# 04-8A34004_DPLL-2.net
KiCad netlist of a schematic drawn in Altium Designer
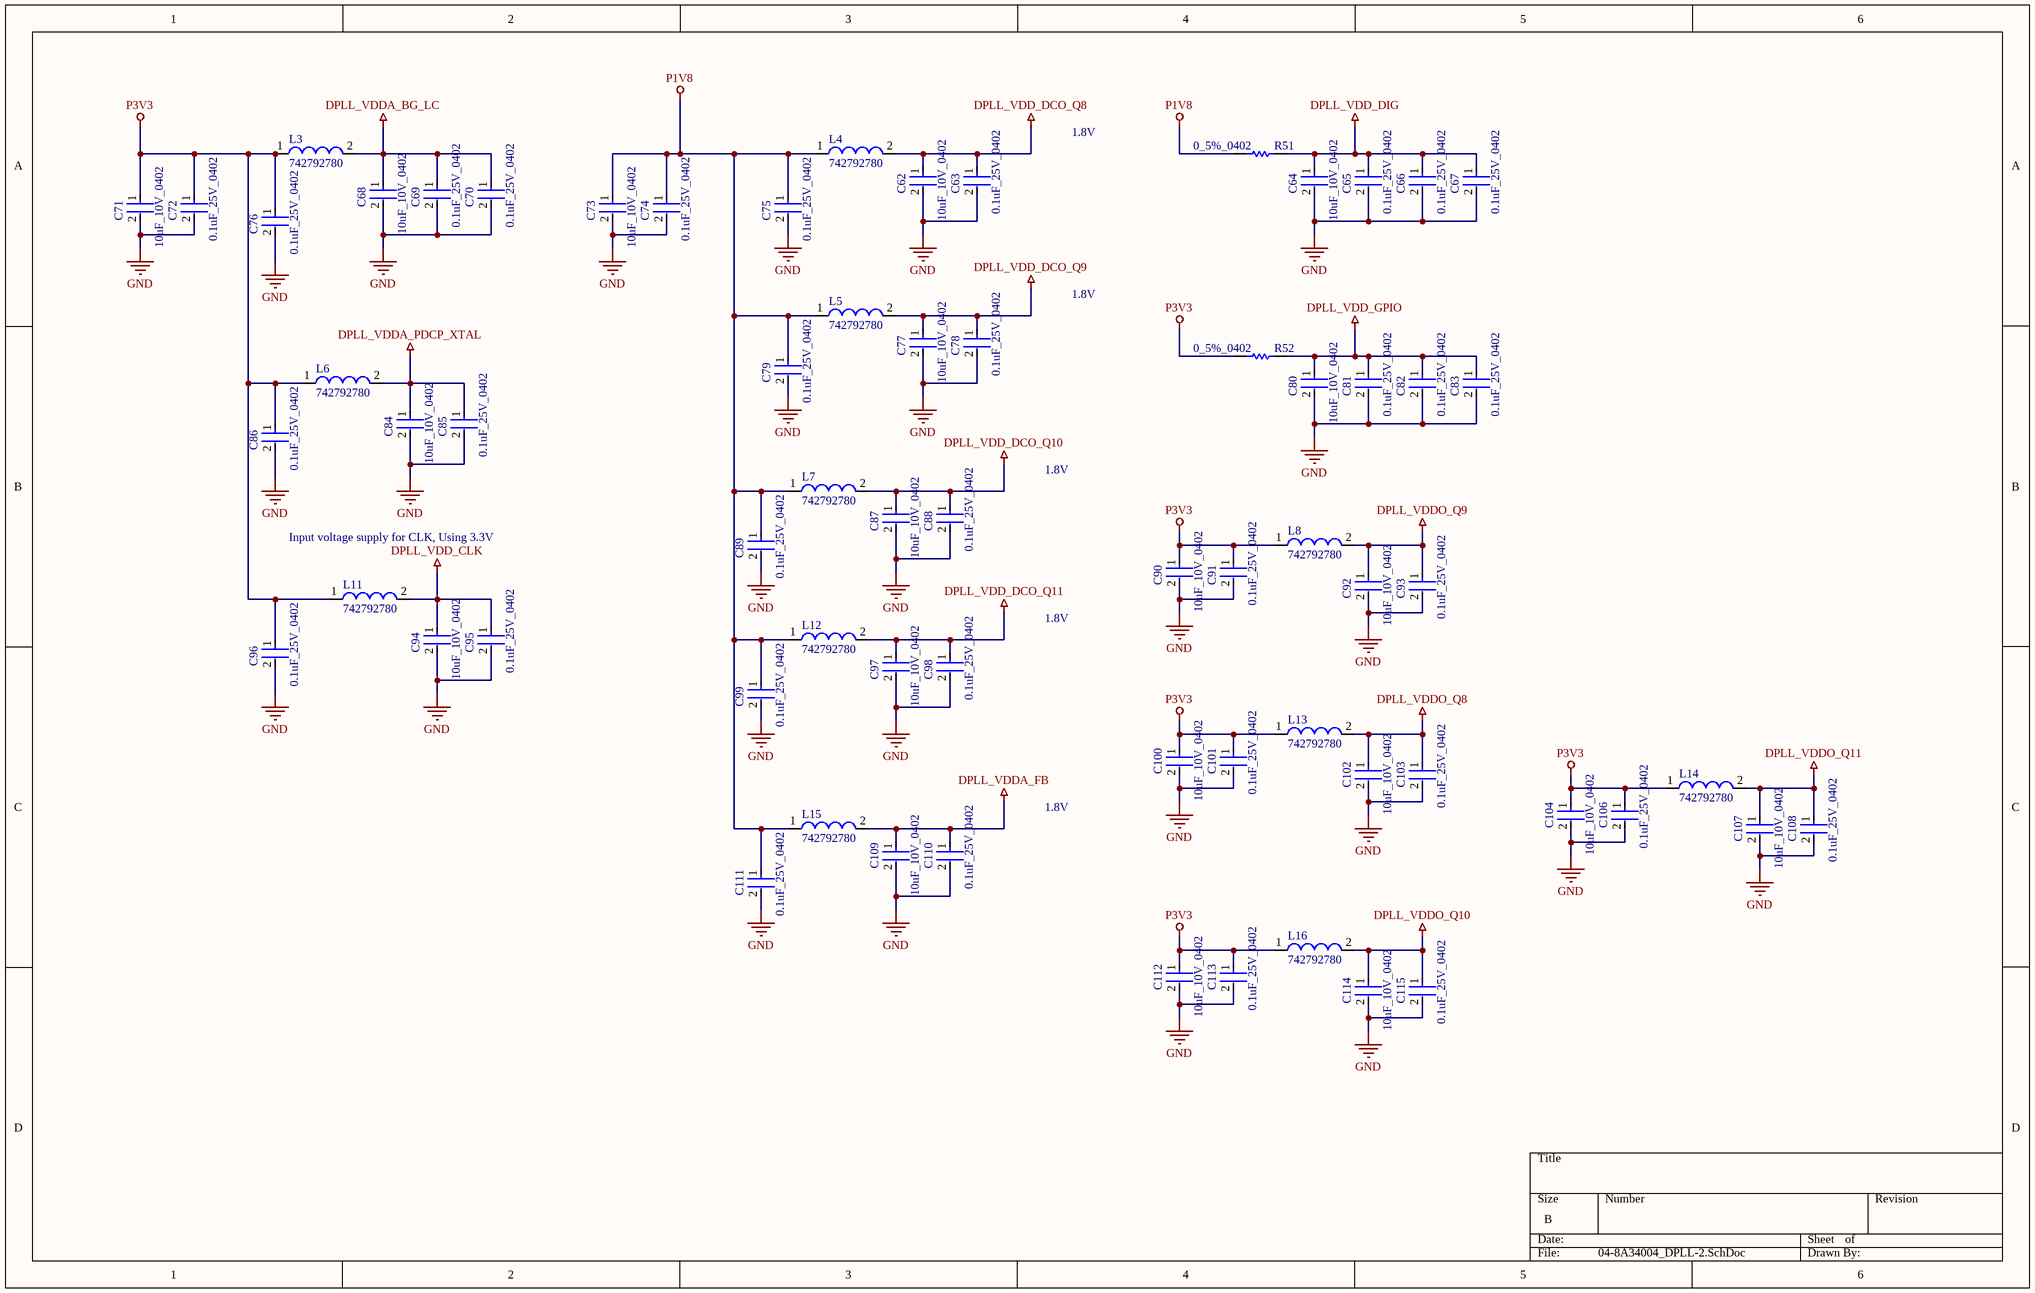
[diagram p0: 04-8A34004_DPLL-2.SchDoc]

(export (version "E")
  (design (tool "Eeschema 10.0.6"))
  (components
    (comp (ref "C62")
      (value "10uF_10V_0402")
      (footprint "FP-CL05A106MP5NUNC-MFG")
      (description "CAP CER 10UF 10V X5R 0402")
      (fields
        (field (name "OCTOPART") "https://octopart.com/cl05a106mp5nunc-samsung-22457395")
        (field (name "TOLERANCE") "20%")
      )
      (libsource (lib "Altium Content Vault") (part "b4654b650e69147ec39a6b967a45e02"))
    )
    (comp (ref "C63")
      (value "0.1uF_25V_0402")
      (footprint "FP-0402-L_1_0_1-W_0_5_0_1-IPC_C")
      (description "General Purpose Ceramic Capacitor, 0402, 100nF, 10%, X7R, 15%, 25V")
      (fields (field (name "VOLTAGE") "25V") (field (name "TOLERANCE") "10%"))
      (libsource (lib "Altium Content Vault") (part "b4654b650e69147ec39a6b967a45e02"))
    )
    (comp (ref "C64")
      (value "10uF_10V_0402")
      (footprint "FP-CL05A106MP5NUNC-MFG")
      (description "CAP CER 10UF 10V X5R 0402")
      (fields
        (field (name "OCTOPART") "https://octopart.com/cl05a106mp5nunc-samsung-22457395")
        (field (name "TOLERANCE") "20%")
      )
      (libsource (lib "Altium Content Vault") (part "b4654b650e69147ec39a6b967a45e02"))
    )
    (comp (ref "C65")
      (value "0.1uF_25V_0402")
      (footprint "FP-0402-L_1_0_1-W_0_5_0_1-IPC_C")
      (description "General Purpose Ceramic Capacitor, 0402, 100nF, 10%, X7R, 15%, 25V")
      (fields (field (name "VOLTAGE") "25V") (field (name "TOLERANCE") "10%"))
      (libsource (lib "Altium Content Vault") (part "b4654b650e69147ec39a6b967a45e02"))
    )
    (comp (ref "C66")
      (value "0.1uF_25V_0402")
      (footprint "FP-0402-L_1_0_1-W_0_5_0_1-IPC_C")
      (description "General Purpose Ceramic Capacitor, 0402, 100nF, 10%, X7R, 15%, 25V")
      (fields (field (name "VOLTAGE") "25V") (field (name "TOLERANCE") "10%"))
      (libsource (lib "Altium Content Vault") (part "b4654b650e69147ec39a6b967a45e02"))
    )
    (comp (ref "C67")
      (value "0.1uF_25V_0402")
      (footprint "FP-0402-L_1_0_1-W_0_5_0_1-IPC_C")
      (description "General Purpose Ceramic Capacitor, 0402, 100nF, 10%, X7R, 15%, 25V")
      (fields (field (name "VOLTAGE") "25V") (field (name "TOLERANCE") "10%"))
      (libsource (lib "Altium Content Vault") (part "b4654b650e69147ec39a6b967a45e02"))
    )
    (comp (ref "C68")
      (value "10uF_10V_0402")
      (footprint "FP-CL05A106MP5NUNC-MFG")
      (description "CAP CER 10UF 10V X5R 0402")
      (fields
        (field (name "OCTOPART") "https://octopart.com/cl05a106mp5nunc-samsung-22457395")
        (field (name "TOLERANCE") "20%")
      )
      (libsource (lib "Altium Content Vault") (part "b4654b650e69147ec39a6b967a45e02"))
    )
    (comp (ref "C69")
      (value "0.1uF_25V_0402")
      (footprint "FP-0402-L_1_0_1-W_0_5_0_1-IPC_C")
      (description "General Purpose Ceramic Capacitor, 0402, 100nF, 10%, X7R, 15%, 25V")
      (fields (field (name "VOLTAGE") "25V") (field (name "TOLERANCE") "10%"))
      (libsource (lib "Altium Content Vault") (part "b4654b650e69147ec39a6b967a45e02"))
    )
    (comp (ref "C70")
      (value "0.1uF_25V_0402")
      (footprint "FP-0402-L_1_0_1-W_0_5_0_1-IPC_C")
      (description "General Purpose Ceramic Capacitor, 0402, 100nF, 10%, X7R, 15%, 25V")
      (fields (field (name "VOLTAGE") "25V") (field (name "TOLERANCE") "10%"))
      (libsource (lib "Altium Content Vault") (part "b4654b650e69147ec39a6b967a45e02"))
    )
    (comp (ref "C71")
      (value "10uF_10V_0402")
      (footprint "FP-CL05A106MP5NUNC-MFG")
      (description "CAP CER 10UF 10V X5R 0402")
      (fields
        (field (name "OCTOPART") "https://octopart.com/cl05a106mp5nunc-samsung-22457395")
        (field (name "TOLERANCE") "20%")
      )
      (libsource (lib "Altium Content Vault") (part "b4654b650e69147ec39a6b967a45e02"))
    )
    (comp (ref "C72")
      (value "0.1uF_25V_0402")
      (footprint "FP-0402-L_1_0_1-W_0_5_0_1-IPC_C")
      (description "General Purpose Ceramic Capacitor, 0402, 100nF, 10%, X7R, 15%, 25V")
      (fields (field (name "VOLTAGE") "25V") (field (name "TOLERANCE") "10%"))
      (libsource (lib "Altium Content Vault") (part "b4654b650e69147ec39a6b967a45e02"))
    )
    (comp (ref "C73")
      (value "10uF_10V_0402")
      (footprint "FP-CL05A106MP5NUNC-MFG")
      (description "CAP CER 10UF 10V X5R 0402")
      (fields
        (field (name "OCTOPART") "https://octopart.com/cl05a106mp5nunc-samsung-22457395")
        (field (name "TOLERANCE") "20%")
      )
      (libsource (lib "Altium Content Vault") (part "b4654b650e69147ec39a6b967a45e02"))
    )
    (comp (ref "C74")
      (value "0.1uF_25V_0402")
      (footprint "FP-0402-L_1_0_1-W_0_5_0_1-IPC_C")
      (description "General Purpose Ceramic Capacitor, 0402, 100nF, 10%, X7R, 15%, 25V")
      (fields (field (name "VOLTAGE") "25V") (field (name "TOLERANCE") "10%"))
      (libsource (lib "Altium Content Vault") (part "b4654b650e69147ec39a6b967a45e02"))
    )
    (comp (ref "C75")
      (value "0.1uF_25V_0402")
      (footprint "FP-0402-L_1_0_1-W_0_5_0_1-IPC_C")
      (description "General Purpose Ceramic Capacitor, 0402, 100nF, 10%, X7R, 15%, 25V")
      (fields (field (name "VOLTAGE") "25V") (field (name "TOLERANCE") "10%"))
      (libsource (lib "Altium Content Vault") (part "b4654b650e69147ec39a6b967a45e02"))
    )
    (comp (ref "C76")
      (value "0.1uF_25V_0402")
      (footprint "FP-0402-L_1_0_1-W_0_5_0_1-IPC_C")
      (description "General Purpose Ceramic Capacitor, 0402, 100nF, 10%, X7R, 15%, 25V")
      (fields (field (name "VOLTAGE") "25V") (field (name "TOLERANCE") "10%"))
      (libsource (lib "Altium Content Vault") (part "b4654b650e69147ec39a6b967a45e02"))
    )
    (comp (ref "C77")
      (value "10uF_10V_0402")
      (footprint "FP-CL05A106MP5NUNC-MFG")
      (description "CAP CER 10UF 10V X5R 0402")
      (fields
        (field (name "OCTOPART") "https://octopart.com/cl05a106mp5nunc-samsung-22457395")
        (field (name "TOLERANCE") "20%")
      )
      (libsource (lib "Altium Content Vault") (part "b4654b650e69147ec39a6b967a45e02"))
    )
    (comp (ref "C78")
      (value "0.1uF_25V_0402")
      (footprint "FP-0402-L_1_0_1-W_0_5_0_1-IPC_C")
      (description "General Purpose Ceramic Capacitor, 0402, 100nF, 10%, X7R, 15%, 25V")
      (fields (field (name "VOLTAGE") "25V") (field (name "TOLERANCE") "10%"))
      (libsource (lib "Altium Content Vault") (part "b4654b650e69147ec39a6b967a45e02"))
    )
    (comp (ref "C79")
      (value "0.1uF_25V_0402")
      (footprint "FP-0402-L_1_0_1-W_0_5_0_1-IPC_C")
      (description "General Purpose Ceramic Capacitor, 0402, 100nF, 10%, X7R, 15%, 25V")
      (fields (field (name "VOLTAGE") "25V") (field (name "TOLERANCE") "10%"))
      (libsource (lib "Altium Content Vault") (part "b4654b650e69147ec39a6b967a45e02"))
    )
    (comp (ref "C80")
      (value "10uF_10V_0402")
      (footprint "FP-CL05A106MP5NUNC-MFG")
      (description "CAP CER 10UF 10V X5R 0402")
      (fields
        (field (name "OCTOPART") "https://octopart.com/cl05a106mp5nunc-samsung-22457395")
        (field (name "TOLERANCE") "20%")
      )
      (libsource (lib "Altium Content Vault") (part "b4654b650e69147ec39a6b967a45e02"))
    )
    (comp (ref "C81")
      (value "0.1uF_25V_0402")
      (footprint "FP-0402-L_1_0_1-W_0_5_0_1-IPC_C")
      (description "General Purpose Ceramic Capacitor, 0402, 100nF, 10%, X7R, 15%, 25V")
      (fields (field (name "VOLTAGE") "25V") (field (name "TOLERANCE") "10%"))
      (libsource (lib "Altium Content Vault") (part "b4654b650e69147ec39a6b967a45e02"))
    )
    (comp (ref "C82")
      (value "0.1uF_25V_0402")
      (footprint "FP-0402-L_1_0_1-W_0_5_0_1-IPC_C")
      (description "General Purpose Ceramic Capacitor, 0402, 100nF, 10%, X7R, 15%, 25V")
      (fields (field (name "VOLTAGE") "25V") (field (name "TOLERANCE") "10%"))
      (libsource (lib "Altium Content Vault") (part "b4654b650e69147ec39a6b967a45e02"))
    )
    (comp (ref "C83")
      (value "0.1uF_25V_0402")
      (footprint "FP-0402-L_1_0_1-W_0_5_0_1-IPC_C")
      (description "General Purpose Ceramic Capacitor, 0402, 100nF, 10%, X7R, 15%, 25V")
      (fields (field (name "VOLTAGE") "25V") (field (name "TOLERANCE") "10%"))
      (libsource (lib "Altium Content Vault") (part "b4654b650e69147ec39a6b967a45e02"))
    )
    (comp (ref "C84")
      (value "10uF_10V_0402")
      (footprint "FP-CL05A106MP5NUNC-MFG")
      (description "CAP CER 10UF 10V X5R 0402")
      (fields
        (field (name "OCTOPART") "https://octopart.com/cl05a106mp5nunc-samsung-22457395")
        (field (name "TOLERANCE") "20%")
      )
      (libsource (lib "Altium Content Vault") (part "b4654b650e69147ec39a6b967a45e02"))
    )
    (comp (ref "C85")
      (value "0.1uF_25V_0402")
      (footprint "FP-0402-L_1_0_1-W_0_5_0_1-IPC_C")
      (description "General Purpose Ceramic Capacitor, 0402, 100nF, 10%, X7R, 15%, 25V")
      (fields (field (name "VOLTAGE") "25V") (field (name "TOLERANCE") "10%"))
      (libsource (lib "Altium Content Vault") (part "b4654b650e69147ec39a6b967a45e02"))
    )
    (comp (ref "C86")
      (value "0.1uF_25V_0402")
      (footprint "FP-0402-L_1_0_1-W_0_5_0_1-IPC_C")
      (description "General Purpose Ceramic Capacitor, 0402, 100nF, 10%, X7R, 15%, 25V")
      (fields (field (name "VOLTAGE") "25V") (field (name "TOLERANCE") "10%"))
      (libsource (lib "Altium Content Vault") (part "b4654b650e69147ec39a6b967a45e02"))
    )
    (comp (ref "C87")
      (value "10uF_10V_0402")
      (footprint "FP-CL05A106MP5NUNC-MFG")
      (description "CAP CER 10UF 10V X5R 0402")
      (fields
        (field (name "OCTOPART") "https://octopart.com/cl05a106mp5nunc-samsung-22457395")
        (field (name "TOLERANCE") "20%")
      )
      (libsource (lib "Altium Content Vault") (part "b4654b650e69147ec39a6b967a45e02"))
    )
    (comp (ref "C88")
      (value "0.1uF_25V_0402")
      (footprint "FP-0402-L_1_0_1-W_0_5_0_1-IPC_C")
      (description "General Purpose Ceramic Capacitor, 0402, 100nF, 10%, X7R, 15%, 25V")
      (fields (field (name "VOLTAGE") "25V") (field (name "TOLERANCE") "10%"))
      (libsource (lib "Altium Content Vault") (part "b4654b650e69147ec39a6b967a45e02"))
    )
    (comp (ref "C89")
      (value "0.1uF_25V_0402")
      (footprint "FP-0402-L_1_0_1-W_0_5_0_1-IPC_C")
      (description "General Purpose Ceramic Capacitor, 0402, 100nF, 10%, X7R, 15%, 25V")
      (fields (field (name "VOLTAGE") "25V") (field (name "TOLERANCE") "10%"))
      (libsource (lib "Altium Content Vault") (part "b4654b650e69147ec39a6b967a45e02"))
    )
    (comp (ref "C90")
      (value "10uF_10V_0402")
      (footprint "FP-CL05A106MP5NUNC-MFG")
      (description "CAP CER 10UF 10V X5R 0402")
      (fields
        (field (name "OCTOPART") "https://octopart.com/cl05a106mp5nunc-samsung-22457395")
        (field (name "TOLERANCE") "20%")
      )
      (libsource (lib "Altium Content Vault") (part "b4654b650e69147ec39a6b967a45e02"))
    )
    (comp (ref "C91")
      (value "0.1uF_25V_0402")
      (footprint "FP-0402-L_1_0_1-W_0_5_0_1-IPC_C")
      (description "General Purpose Ceramic Capacitor, 0402, 100nF, 10%, X7R, 15%, 25V")
      (fields (field (name "VOLTAGE") "25V") (field (name "TOLERANCE") "10%"))
      (libsource (lib "Altium Content Vault") (part "b4654b650e69147ec39a6b967a45e02"))
    )
    (comp (ref "C92")
      (value "10uF_10V_0402")
      (footprint "FP-CL05A106MP5NUNC-MFG")
      (description "CAP CER 10UF 10V X5R 0402")
      (fields
        (field (name "OCTOPART") "https://octopart.com/cl05a106mp5nunc-samsung-22457395")
        (field (name "TOLERANCE") "20%")
      )
      (libsource (lib "Altium Content Vault") (part "b4654b650e69147ec39a6b967a45e02"))
    )
    (comp (ref "C93")
      (value "0.1uF_25V_0402")
      (footprint "FP-0402-L_1_0_1-W_0_5_0_1-IPC_C")
      (description "General Purpose Ceramic Capacitor, 0402, 100nF, 10%, X7R, 15%, 25V")
      (fields (field (name "VOLTAGE") "25V") (field (name "TOLERANCE") "10%"))
      (libsource (lib "Altium Content Vault") (part "b4654b650e69147ec39a6b967a45e02"))
    )
    (comp (ref "C94")
      (value "10uF_10V_0402")
      (footprint "FP-CL05A106MP5NUNC-MFG")
      (description "CAP CER 10UF 10V X5R 0402")
      (fields
        (field (name "OCTOPART") "https://octopart.com/cl05a106mp5nunc-samsung-22457395")
        (field (name "TOLERANCE") "20%")
      )
      (libsource (lib "Altium Content Vault") (part "b4654b650e69147ec39a6b967a45e02"))
    )
    (comp (ref "C95")
      (value "0.1uF_25V_0402")
      (footprint "FP-0402-L_1_0_1-W_0_5_0_1-IPC_C")
      (description "General Purpose Ceramic Capacitor, 0402, 100nF, 10%, X7R, 15%, 25V")
      (fields (field (name "VOLTAGE") "25V") (field (name "TOLERANCE") "10%"))
      (libsource (lib "Altium Content Vault") (part "b4654b650e69147ec39a6b967a45e02"))
    )
    (comp (ref "C96")
      (value "0.1uF_25V_0402")
      (footprint "FP-0402-L_1_0_1-W_0_5_0_1-IPC_C")
      (description "General Purpose Ceramic Capacitor, 0402, 100nF, 10%, X7R, 15%, 25V")
      (fields (field (name "VOLTAGE") "25V") (field (name "TOLERANCE") "10%"))
      (libsource (lib "Altium Content Vault") (part "b4654b650e69147ec39a6b967a45e02"))
    )
    (comp (ref "C97")
      (value "10uF_10V_0402")
      (footprint "FP-CL05A106MP5NUNC-MFG")
      (description "CAP CER 10UF 10V X5R 0402")
      (fields
        (field (name "OCTOPART") "https://octopart.com/cl05a106mp5nunc-samsung-22457395")
        (field (name "TOLERANCE") "20%")
      )
      (libsource (lib "Altium Content Vault") (part "b4654b650e69147ec39a6b967a45e02"))
    )
    (comp (ref "C98")
      (value "0.1uF_25V_0402")
      (footprint "FP-0402-L_1_0_1-W_0_5_0_1-IPC_C")
      (description "General Purpose Ceramic Capacitor, 0402, 100nF, 10%, X7R, 15%, 25V")
      (fields (field (name "VOLTAGE") "25V") (field (name "TOLERANCE") "10%"))
      (libsource (lib "Altium Content Vault") (part "b4654b650e69147ec39a6b967a45e02"))
    )
    (comp (ref "C99")
      (value "0.1uF_25V_0402")
      (footprint "FP-0402-L_1_0_1-W_0_5_0_1-IPC_C")
      (description "General Purpose Ceramic Capacitor, 0402, 100nF, 10%, X7R, 15%, 25V")
      (fields (field (name "VOLTAGE") "25V") (field (name "TOLERANCE") "10%"))
      (libsource (lib "Altium Content Vault") (part "b4654b650e69147ec39a6b967a45e02"))
    )
    (comp (ref "C100")
      (value "10uF_10V_0402")
      (footprint "FP-CL05A106MP5NUNC-MFG")
      (description "CAP CER 10UF 10V X5R 0402")
      (fields
        (field (name "OCTOPART") "https://octopart.com/cl05a106mp5nunc-samsung-22457395")
        (field (name "TOLERANCE") "20%")
      )
      (libsource (lib "Altium Content Vault") (part "b4654b650e69147ec39a6b967a45e02"))
    )
    (comp (ref "C101")
      (value "0.1uF_25V_0402")
      (footprint "FP-0402-L_1_0_1-W_0_5_0_1-IPC_C")
      (description "General Purpose Ceramic Capacitor, 0402, 100nF, 10%, X7R, 15%, 25V")
      (fields (field (name "VOLTAGE") "25V") (field (name "TOLERANCE") "10%"))
      (libsource (lib "Altium Content Vault") (part "b4654b650e69147ec39a6b967a45e02"))
    )
    (comp (ref "C102")
      (value "10uF_10V_0402")
      (footprint "FP-CL05A106MP5NUNC-MFG")
      (description "CAP CER 10UF 10V X5R 0402")
      (fields
        (field (name "OCTOPART") "https://octopart.com/cl05a106mp5nunc-samsung-22457395")
        (field (name "TOLERANCE") "20%")
      )
      (libsource (lib "Altium Content Vault") (part "b4654b650e69147ec39a6b967a45e02"))
    )
    (comp (ref "C103")
      (value "0.1uF_25V_0402")
      (footprint "FP-0402-L_1_0_1-W_0_5_0_1-IPC_C")
      (description "General Purpose Ceramic Capacitor, 0402, 100nF, 10%, X7R, 15%, 25V")
      (fields (field (name "VOLTAGE") "25V") (field (name "TOLERANCE") "10%"))
      (libsource (lib "Altium Content Vault") (part "b4654b650e69147ec39a6b967a45e02"))
    )
    (comp (ref "C104")
      (value "10uF_10V_0402")
      (footprint "FP-CL05A106MP5NUNC-MFG")
      (description "CAP CER 10UF 10V X5R 0402")
      (fields
        (field (name "OCTOPART") "https://octopart.com/cl05a106mp5nunc-samsung-22457395")
        (field (name "TOLERANCE") "20%")
      )
      (libsource (lib "Altium Content Vault") (part "b4654b650e69147ec39a6b967a45e02"))
    )
    (comp (ref "C106")
      (value "0.1uF_25V_0402")
      (footprint "FP-0402-L_1_0_1-W_0_5_0_1-IPC_C")
      (description "General Purpose Ceramic Capacitor, 0402, 100nF, 10%, X7R, 15%, 25V")
      (fields (field (name "VOLTAGE") "25V") (field (name "TOLERANCE") "10%"))
      (libsource (lib "Altium Content Vault") (part "b4654b650e69147ec39a6b967a45e02"))
    )
    (comp (ref "C107")
      (value "10uF_10V_0402")
      (footprint "FP-CL05A106MP5NUNC-MFG")
      (description "CAP CER 10UF 10V X5R 0402")
      (fields
        (field (name "OCTOPART") "https://octopart.com/cl05a106mp5nunc-samsung-22457395")
        (field (name "TOLERANCE") "20%")
      )
      (libsource (lib "Altium Content Vault") (part "b4654b650e69147ec39a6b967a45e02"))
    )
    (comp (ref "C108")
      (value "0.1uF_25V_0402")
      (footprint "FP-0402-L_1_0_1-W_0_5_0_1-IPC_C")
      (description "General Purpose Ceramic Capacitor, 0402, 100nF, 10%, X7R, 15%, 25V")
      (fields (field (name "VOLTAGE") "25V") (field (name "TOLERANCE") "10%"))
      (libsource (lib "Altium Content Vault") (part "b4654b650e69147ec39a6b967a45e02"))
    )
    (comp (ref "C109")
      (value "10uF_10V_0402")
      (footprint "FP-CL05A106MP5NUNC-MFG")
      (description "CAP CER 10UF 10V X5R 0402")
      (fields
        (field (name "OCTOPART") "https://octopart.com/cl05a106mp5nunc-samsung-22457395")
        (field (name "TOLERANCE") "20%")
      )
      (libsource (lib "Altium Content Vault") (part "b4654b650e69147ec39a6b967a45e02"))
    )
    (comp (ref "C110")
      (value "0.1uF_25V_0402")
      (footprint "FP-0402-L_1_0_1-W_0_5_0_1-IPC_C")
      (description "General Purpose Ceramic Capacitor, 0402, 100nF, 10%, X7R, 15%, 25V")
      (fields (field (name "VOLTAGE") "25V") (field (name "TOLERANCE") "10%"))
      (libsource (lib "Altium Content Vault") (part "b4654b650e69147ec39a6b967a45e02"))
    )
    (comp (ref "C111")
      (value "0.1uF_25V_0402")
      (footprint "FP-0402-L_1_0_1-W_0_5_0_1-IPC_C")
      (description "General Purpose Ceramic Capacitor, 0402, 100nF, 10%, X7R, 15%, 25V")
      (fields (field (name "VOLTAGE") "25V") (field (name "TOLERANCE") "10%"))
      (libsource (lib "Altium Content Vault") (part "b4654b650e69147ec39a6b967a45e02"))
    )
    (comp (ref "C112")
      (value "10uF_10V_0402")
      (footprint "FP-CL05A106MP5NUNC-MFG")
      (description "CAP CER 10UF 10V X5R 0402")
      (fields
        (field (name "OCTOPART") "https://octopart.com/cl05a106mp5nunc-samsung-22457395")
        (field (name "TOLERANCE") "20%")
      )
      (libsource (lib "Altium Content Vault") (part "b4654b650e69147ec39a6b967a45e02"))
    )
    (comp (ref "C113")
      (value "0.1uF_25V_0402")
      (footprint "FP-0402-L_1_0_1-W_0_5_0_1-IPC_C")
      (description "General Purpose Ceramic Capacitor, 0402, 100nF, 10%, X7R, 15%, 25V")
      (fields (field (name "VOLTAGE") "25V") (field (name "TOLERANCE") "10%"))
      (libsource (lib "Altium Content Vault") (part "b4654b650e69147ec39a6b967a45e02"))
    )
    (comp (ref "C114")
      (value "10uF_10V_0402")
      (footprint "FP-CL05A106MP5NUNC-MFG")
      (description "CAP CER 10UF 10V X5R 0402")
      (fields
        (field (name "OCTOPART") "https://octopart.com/cl05a106mp5nunc-samsung-22457395")
        (field (name "TOLERANCE") "20%")
      )
      (libsource (lib "Altium Content Vault") (part "b4654b650e69147ec39a6b967a45e02"))
    )
    (comp (ref "C115")
      (value "0.1uF_25V_0402")
      (footprint "FP-0402-L_1_0_1-W_0_5_0_1-IPC_C")
      (description "General Purpose Ceramic Capacitor, 0402, 100nF, 10%, X7R, 15%, 25V")
      (fields (field (name "VOLTAGE") "25V") (field (name "TOLERANCE") "10%"))
      (libsource (lib "Altium Content Vault") (part "b4654b650e69147ec39a6b967a45e02"))
    )
    (comp (ref "L3")
      (value "742792780")
      (footprint "SMD-0402")
      (description "SMD EMI Suppression Ferrite Bead WE-CBF, Z = 220 Ohm")
      (libsource (lib "Altium Content Vault") (part "PAS-IND-INDUCTOR-2"))
    )
    (comp (ref "L4")
      (value "742792780")
      (footprint "SMD-0402")
      (description "SMD EMI Suppression Ferrite Bead WE-CBF, Z = 220 Ohm")
      (libsource (lib "Altium Content Vault") (part "PAS-IND-INDUCTOR-2"))
    )
    (comp (ref "L5")
      (value "742792780")
      (footprint "SMD-0402")
      (description "SMD EMI Suppression Ferrite Bead WE-CBF, Z = 220 Ohm")
      (libsource (lib "Altium Content Vault") (part "PAS-IND-INDUCTOR-2"))
    )
    (comp (ref "L6")
      (value "742792780")
      (footprint "SMD-0402")
      (description "SMD EMI Suppression Ferrite Bead WE-CBF, Z = 220 Ohm")
      (libsource (lib "Altium Content Vault") (part "PAS-IND-INDUCTOR-2"))
    )
    (comp (ref "L7")
      (value "742792780")
      (footprint "SMD-0402")
      (description "SMD EMI Suppression Ferrite Bead WE-CBF, Z = 220 Ohm")
      (libsource (lib "Altium Content Vault") (part "PAS-IND-INDUCTOR-2"))
    )
    (comp (ref "L8")
      (value "742792780")
      (footprint "SMD-0402")
      (description "SMD EMI Suppression Ferrite Bead WE-CBF, Z = 220 Ohm")
      (libsource (lib "Altium Content Vault") (part "PAS-IND-INDUCTOR-2"))
    )
    (comp (ref "L11")
      (value "742792780")
      (footprint "SMD-0402")
      (description "SMD EMI Suppression Ferrite Bead WE-CBF, Z = 220 Ohm")
      (libsource (lib "Altium Content Vault") (part "PAS-IND-INDUCTOR-2"))
    )
    (comp (ref "L12")
      (value "742792780")
      (footprint "SMD-0402")
      (description "SMD EMI Suppression Ferrite Bead WE-CBF, Z = 220 Ohm")
      (libsource (lib "Altium Content Vault") (part "PAS-IND-INDUCTOR-2"))
    )
    (comp (ref "L13")
      (value "742792780")
      (footprint "SMD-0402")
      (description "SMD EMI Suppression Ferrite Bead WE-CBF, Z = 220 Ohm")
      (libsource (lib "Altium Content Vault") (part "PAS-IND-INDUCTOR-2"))
    )
    (comp (ref "L14")
      (value "742792780")
      (footprint "SMD-0402")
      (description "SMD EMI Suppression Ferrite Bead WE-CBF, Z = 220 Ohm")
      (libsource (lib "Altium Content Vault") (part "PAS-IND-INDUCTOR-2"))
    )
    (comp (ref "L15")
      (value "742792780")
      (footprint "SMD-0402")
      (description "SMD EMI Suppression Ferrite Bead WE-CBF, Z = 220 Ohm")
      (libsource (lib "Altium Content Vault") (part "PAS-IND-INDUCTOR-2"))
    )
    (comp (ref "L16")
      (value "742792780")
      (footprint "SMD-0402")
      (description "SMD EMI Suppression Ferrite Bead WE-CBF, Z = 220 Ohm")
      (libsource (lib "Altium Content Vault") (part "PAS-IND-INDUCTOR-2"))
    )
    (comp (ref "R51")
      (value "0_5%_0402")
      (footprint "RESC1005X40X25LL10T10")
      (fields (field (name "MANUFACTURER") "KOA Speer") (field (name "PART NUMBER") "RK73Z1ETTP"))
      (libsource (lib "Altium Content Vault") (part "RES"))
    )
    (comp (ref "R52")
      (value "0_5%_0402")
      (footprint "RESC1005X40X25LL10T10")
      (fields (field (name "MANUFACTURER") "KOA Speer") (field (name "PART NUMBER") "RK73Z1ETTP"))
      (libsource (lib "Altium Content Vault") (part "RES"))
    )
  )
  (nets
    (net (code "1") (name "DPLL_VDDA_BG_LC") (class "Default")
      (node (ref "C68") (pin "1") (pinfunction "1_1") (pintype "passive"))
      (node (ref "C69") (pin "1") (pinfunction "1_1") (pintype "passive"))
      (node (ref "C70") (pin "1") (pinfunction "1_1") (pintype "passive"))
      (node (ref "L3") (pin "2") (pinfunction "2_2") (pintype "passive"))
    )
    (net (code "2") (name "DPLL_VDDA_FB") (class "Default")
      (node (ref "C109") (pin "1") (pinfunction "1_1") (pintype "passive"))
      (node (ref "C110") (pin "1") (pinfunction "1_1") (pintype "passive"))
      (node (ref "L15") (pin "2") (pinfunction "2_2") (pintype "passive"))
    )
    (net (code "3") (name "DPLL_VDDA_PDCP_XTAL") (class "Default")
      (node (ref "C84") (pin "1") (pinfunction "1_1") (pintype "passive"))
      (node (ref "C85") (pin "1") (pinfunction "1_1") (pintype "passive"))
      (node (ref "L6") (pin "2") (pinfunction "2_2") (pintype "passive"))
    )
    (net (code "4") (name "DPLL_VDDO_Q8") (class "Default")
      (node (ref "C102") (pin "1") (pinfunction "1_1") (pintype "passive"))
      (node (ref "C103") (pin "1") (pinfunction "1_1") (pintype "passive"))
      (node (ref "L13") (pin "2") (pinfunction "2_2") (pintype "passive"))
    )
    (net (code "5") (name "DPLL_VDDO_Q9") (class "Default")
      (node (ref "C92") (pin "1") (pinfunction "1_1") (pintype "passive"))
      (node (ref "C93") (pin "1") (pinfunction "1_1") (pintype "passive"))
      (node (ref "L8") (pin "2") (pinfunction "2_2") (pintype "passive"))
    )
    (net (code "6") (name "DPLL_VDDO_Q10") (class "Default")
      (node (ref "C114") (pin "1") (pinfunction "1_1") (pintype "passive"))
      (node (ref "C115") (pin "1") (pinfunction "1_1") (pintype "passive"))
      (node (ref "L16") (pin "2") (pinfunction "2_2") (pintype "passive"))
    )
    (net (code "7") (name "DPLL_VDDO_Q11") (class "Default")
      (node (ref "C107") (pin "1") (pinfunction "1_1") (pintype "passive"))
      (node (ref "C108") (pin "1") (pinfunction "1_1") (pintype "passive"))
      (node (ref "L14") (pin "2") (pinfunction "2_2") (pintype "passive"))
    )
    (net (code "8") (name "DPLL_VDD_CLK") (class "Default")
      (node (ref "C94") (pin "1") (pinfunction "1_1") (pintype "passive"))
      (node (ref "C95") (pin "1") (pinfunction "1_1") (pintype "passive"))
      (node (ref "L11") (pin "2") (pinfunction "2_2") (pintype "passive"))
    )
    (net (code "9") (name "DPLL_VDD_DCO_Q8") (class "Default")
      (node (ref "C62") (pin "1") (pinfunction "1_1") (pintype "passive"))
      (node (ref "C63") (pin "1") (pinfunction "1_1") (pintype "passive"))
      (node (ref "L4") (pin "2") (pinfunction "2_2") (pintype "passive"))
    )
    (net (code "10") (name "DPLL_VDD_DCO_Q9") (class "Default")
      (node (ref "C77") (pin "1") (pinfunction "1_1") (pintype "passive"))
      (node (ref "C78") (pin "1") (pinfunction "1_1") (pintype "passive"))
      (node (ref "L5") (pin "2") (pinfunction "2_2") (pintype "passive"))
    )
    (net (code "11") (name "DPLL_VDD_DCO_Q10") (class "Default")
      (node (ref "C87") (pin "1") (pinfunction "1_1") (pintype "passive"))
      (node (ref "C88") (pin "1") (pinfunction "1_1") (pintype "passive"))
      (node (ref "L7") (pin "2") (pinfunction "2_2") (pintype "passive"))
    )
    (net (code "12") (name "DPLL_VDD_DCO_Q11") (class "Default")
      (node (ref "C97") (pin "1") (pinfunction "1_1") (pintype "passive"))
      (node (ref "C98") (pin "1") (pinfunction "1_1") (pintype "passive"))
      (node (ref "L12") (pin "2") (pinfunction "2_2") (pintype "passive"))
    )
    (net (code "13") (name "DPLL_VDD_DIG") (class "Default")
      (node (ref "C64") (pin "1") (pinfunction "1_1") (pintype "passive"))
      (node (ref "C65") (pin "1") (pinfunction "1_1") (pintype "passive"))
      (node (ref "C66") (pin "1") (pinfunction "1_1") (pintype "passive"))
      (node (ref "C67") (pin "1") (pinfunction "1_1") (pintype "passive"))
      (node (ref "R51") (pin "2") (pinfunction "2_2") (pintype "passive"))
    )
    (net (code "14") (name "DPLL_VDD_GPIO") (class "Default")
      (node (ref "C80") (pin "1") (pinfunction "1_1") (pintype "passive"))
      (node (ref "C81") (pin "1") (pinfunction "1_1") (pintype "passive"))
      (node (ref "C82") (pin "1") (pinfunction "1_1") (pintype "passive"))
      (node (ref "C83") (pin "1") (pinfunction "1_1") (pintype "passive"))
      (node (ref "R52") (pin "2") (pinfunction "2_2") (pintype "passive"))
    )
    (net (code "15") (name "GND") (class "Default")
      (node (ref "C100") (pin "2") (pinfunction "2_2") (pintype "passive"))
      (node (ref "C101") (pin "2") (pinfunction "2_2") (pintype "passive"))
      (node (ref "C102") (pin "2") (pinfunction "2_2") (pintype "passive"))
      (node (ref "C103") (pin "2") (pinfunction "2_2") (pintype "passive"))
      (node (ref "C104") (pin "2") (pinfunction "2_2") (pintype "passive"))
      (node (ref "C106") (pin "2") (pinfunction "2_2") (pintype "passive"))
      (node (ref "C107") (pin "2") (pinfunction "2_2") (pintype "passive"))
      (node (ref "C108") (pin "2") (pinfunction "2_2") (pintype "passive"))
      (node (ref "C109") (pin "2") (pinfunction "2_2") (pintype "passive"))
      (node (ref "C110") (pin "2") (pinfunction "2_2") (pintype "passive"))
      (node (ref "C111") (pin "2") (pinfunction "2_2") (pintype "passive"))
      (node (ref "C112") (pin "2") (pinfunction "2_2") (pintype "passive"))
      (node (ref "C113") (pin "2") (pinfunction "2_2") (pintype "passive"))
      (node (ref "C114") (pin "2") (pinfunction "2_2") (pintype "passive"))
      (node (ref "C115") (pin "2") (pinfunction "2_2") (pintype "passive"))
      (node (ref "C62") (pin "2") (pinfunction "2_2") (pintype "passive"))
      (node (ref "C63") (pin "2") (pinfunction "2_2") (pintype "passive"))
      (node (ref "C64") (pin "2") (pinfunction "2_2") (pintype "passive"))
      (node (ref "C65") (pin "2") (pinfunction "2_2") (pintype "passive"))
      (node (ref "C66") (pin "2") (pinfunction "2_2") (pintype "passive"))
      (node (ref "C67") (pin "2") (pinfunction "2_2") (pintype "passive"))
      (node (ref "C68") (pin "2") (pinfunction "2_2") (pintype "passive"))
      (node (ref "C69") (pin "2") (pinfunction "2_2") (pintype "passive"))
      (node (ref "C70") (pin "2") (pinfunction "2_2") (pintype "passive"))
      (node (ref "C71") (pin "2") (pinfunction "2_2") (pintype "passive"))
      (node (ref "C72") (pin "2") (pinfunction "2_2") (pintype "passive"))
      (node (ref "C73") (pin "2") (pinfunction "2_2") (pintype "passive"))
      (node (ref "C74") (pin "2") (pinfunction "2_2") (pintype "passive"))
      (node (ref "C75") (pin "2") (pinfunction "2_2") (pintype "passive"))
      (node (ref "C76") (pin "2") (pinfunction "2_2") (pintype "passive"))
      (node (ref "C77") (pin "2") (pinfunction "2_2") (pintype "passive"))
      (node (ref "C78") (pin "2") (pinfunction "2_2") (pintype "passive"))
      (node (ref "C79") (pin "2") (pinfunction "2_2") (pintype "passive"))
      (node (ref "C80") (pin "2") (pinfunction "2_2") (pintype "passive"))
      (node (ref "C81") (pin "2") (pinfunction "2_2") (pintype "passive"))
      (node (ref "C82") (pin "2") (pinfunction "2_2") (pintype "passive"))
      (node (ref "C83") (pin "2") (pinfunction "2_2") (pintype "passive"))
      (node (ref "C84") (pin "2") (pinfunction "2_2") (pintype "passive"))
      (node (ref "C85") (pin "2") (pinfunction "2_2") (pintype "passive"))
      (node (ref "C86") (pin "2") (pinfunction "2_2") (pintype "passive"))
      (node (ref "C87") (pin "2") (pinfunction "2_2") (pintype "passive"))
      (node (ref "C88") (pin "2") (pinfunction "2_2") (pintype "passive"))
      (node (ref "C89") (pin "2") (pinfunction "2_2") (pintype "passive"))
      (node (ref "C90") (pin "2") (pinfunction "2_2") (pintype "passive"))
      (node (ref "C91") (pin "2") (pinfunction "2_2") (pintype "passive"))
      (node (ref "C92") (pin "2") (pinfunction "2_2") (pintype "passive"))
      (node (ref "C93") (pin "2") (pinfunction "2_2") (pintype "passive"))
      (node (ref "C94") (pin "2") (pinfunction "2_2") (pintype "passive"))
      (node (ref "C95") (pin "2") (pinfunction "2_2") (pintype "passive"))
      (node (ref "C96") (pin "2") (pinfunction "2_2") (pintype "passive"))
      (node (ref "C97") (pin "2") (pinfunction "2_2") (pintype "passive"))
      (node (ref "C98") (pin "2") (pinfunction "2_2") (pintype "passive"))
      (node (ref "C99") (pin "2") (pinfunction "2_2") (pintype "passive"))
    )
    (net (code "16") (name "P1V8") (class "Default")
      (node (ref "C111") (pin "1") (pinfunction "1_1") (pintype "passive"))
      (node (ref "C73") (pin "1") (pinfunction "1_1") (pintype "passive"))
      (node (ref "C74") (pin "1") (pinfunction "1_1") (pintype "passive"))
      (node (ref "C75") (pin "1") (pinfunction "1_1") (pintype "passive"))
      (node (ref "C79") (pin "1") (pinfunction "1_1") (pintype "passive"))
      (node (ref "C89") (pin "1") (pinfunction "1_1") (pintype "passive"))
      (node (ref "C99") (pin "1") (pinfunction "1_1") (pintype "passive"))
      (node (ref "L12") (pin "1") (pinfunction "1_1") (pintype "passive"))
      (node (ref "L15") (pin "1") (pinfunction "1_1") (pintype "passive"))
      (node (ref "L4") (pin "1") (pinfunction "1_1") (pintype "passive"))
      (node (ref "L5") (pin "1") (pinfunction "1_1") (pintype "passive"))
      (node (ref "L7") (pin "1") (pinfunction "1_1") (pintype "passive"))
      (node (ref "R51") (pin "1") (pinfunction "1_1") (pintype "passive"))
    )
    (net (code "17") (name "P3V3") (class "Default")
      (node (ref "C100") (pin "1") (pinfunction "1_1") (pintype "passive"))
      (node (ref "C101") (pin "1") (pinfunction "1_1") (pintype "passive"))
      (node (ref "C104") (pin "1") (pinfunction "1_1") (pintype "passive"))
      (node (ref "C106") (pin "1") (pinfunction "1_1") (pintype "passive"))
      (node (ref "C112") (pin "1") (pinfunction "1_1") (pintype "passive"))
      (node (ref "C113") (pin "1") (pinfunction "1_1") (pintype "passive"))
      (node (ref "C71") (pin "1") (pinfunction "1_1") (pintype "passive"))
      (node (ref "C72") (pin "1") (pinfunction "1_1") (pintype "passive"))
      (node (ref "C76") (pin "1") (pinfunction "1_1") (pintype "passive"))
      (node (ref "C86") (pin "1") (pinfunction "1_1") (pintype "passive"))
      (node (ref "C90") (pin "1") (pinfunction "1_1") (pintype "passive"))
      (node (ref "C91") (pin "1") (pinfunction "1_1") (pintype "passive"))
      (node (ref "C96") (pin "1") (pinfunction "1_1") (pintype "passive"))
      (node (ref "L11") (pin "1") (pinfunction "1_1") (pintype "passive"))
      (node (ref "L13") (pin "1") (pinfunction "1_1") (pintype "passive"))
      (node (ref "L14") (pin "1") (pinfunction "1_1") (pintype "passive"))
      (node (ref "L16") (pin "1") (pinfunction "1_1") (pintype "passive"))
      (node (ref "L3") (pin "1") (pinfunction "1_1") (pintype "passive"))
      (node (ref "L6") (pin "1") (pinfunction "1_1") (pintype "passive"))
      (node (ref "L8") (pin "1") (pinfunction "1_1") (pintype "passive"))
      (node (ref "R52") (pin "1") (pinfunction "1_1") (pintype "passive"))
    )
  )
)
